# WSN_v2.net
KiCad netlist of a schematic drawn in Altium Designer
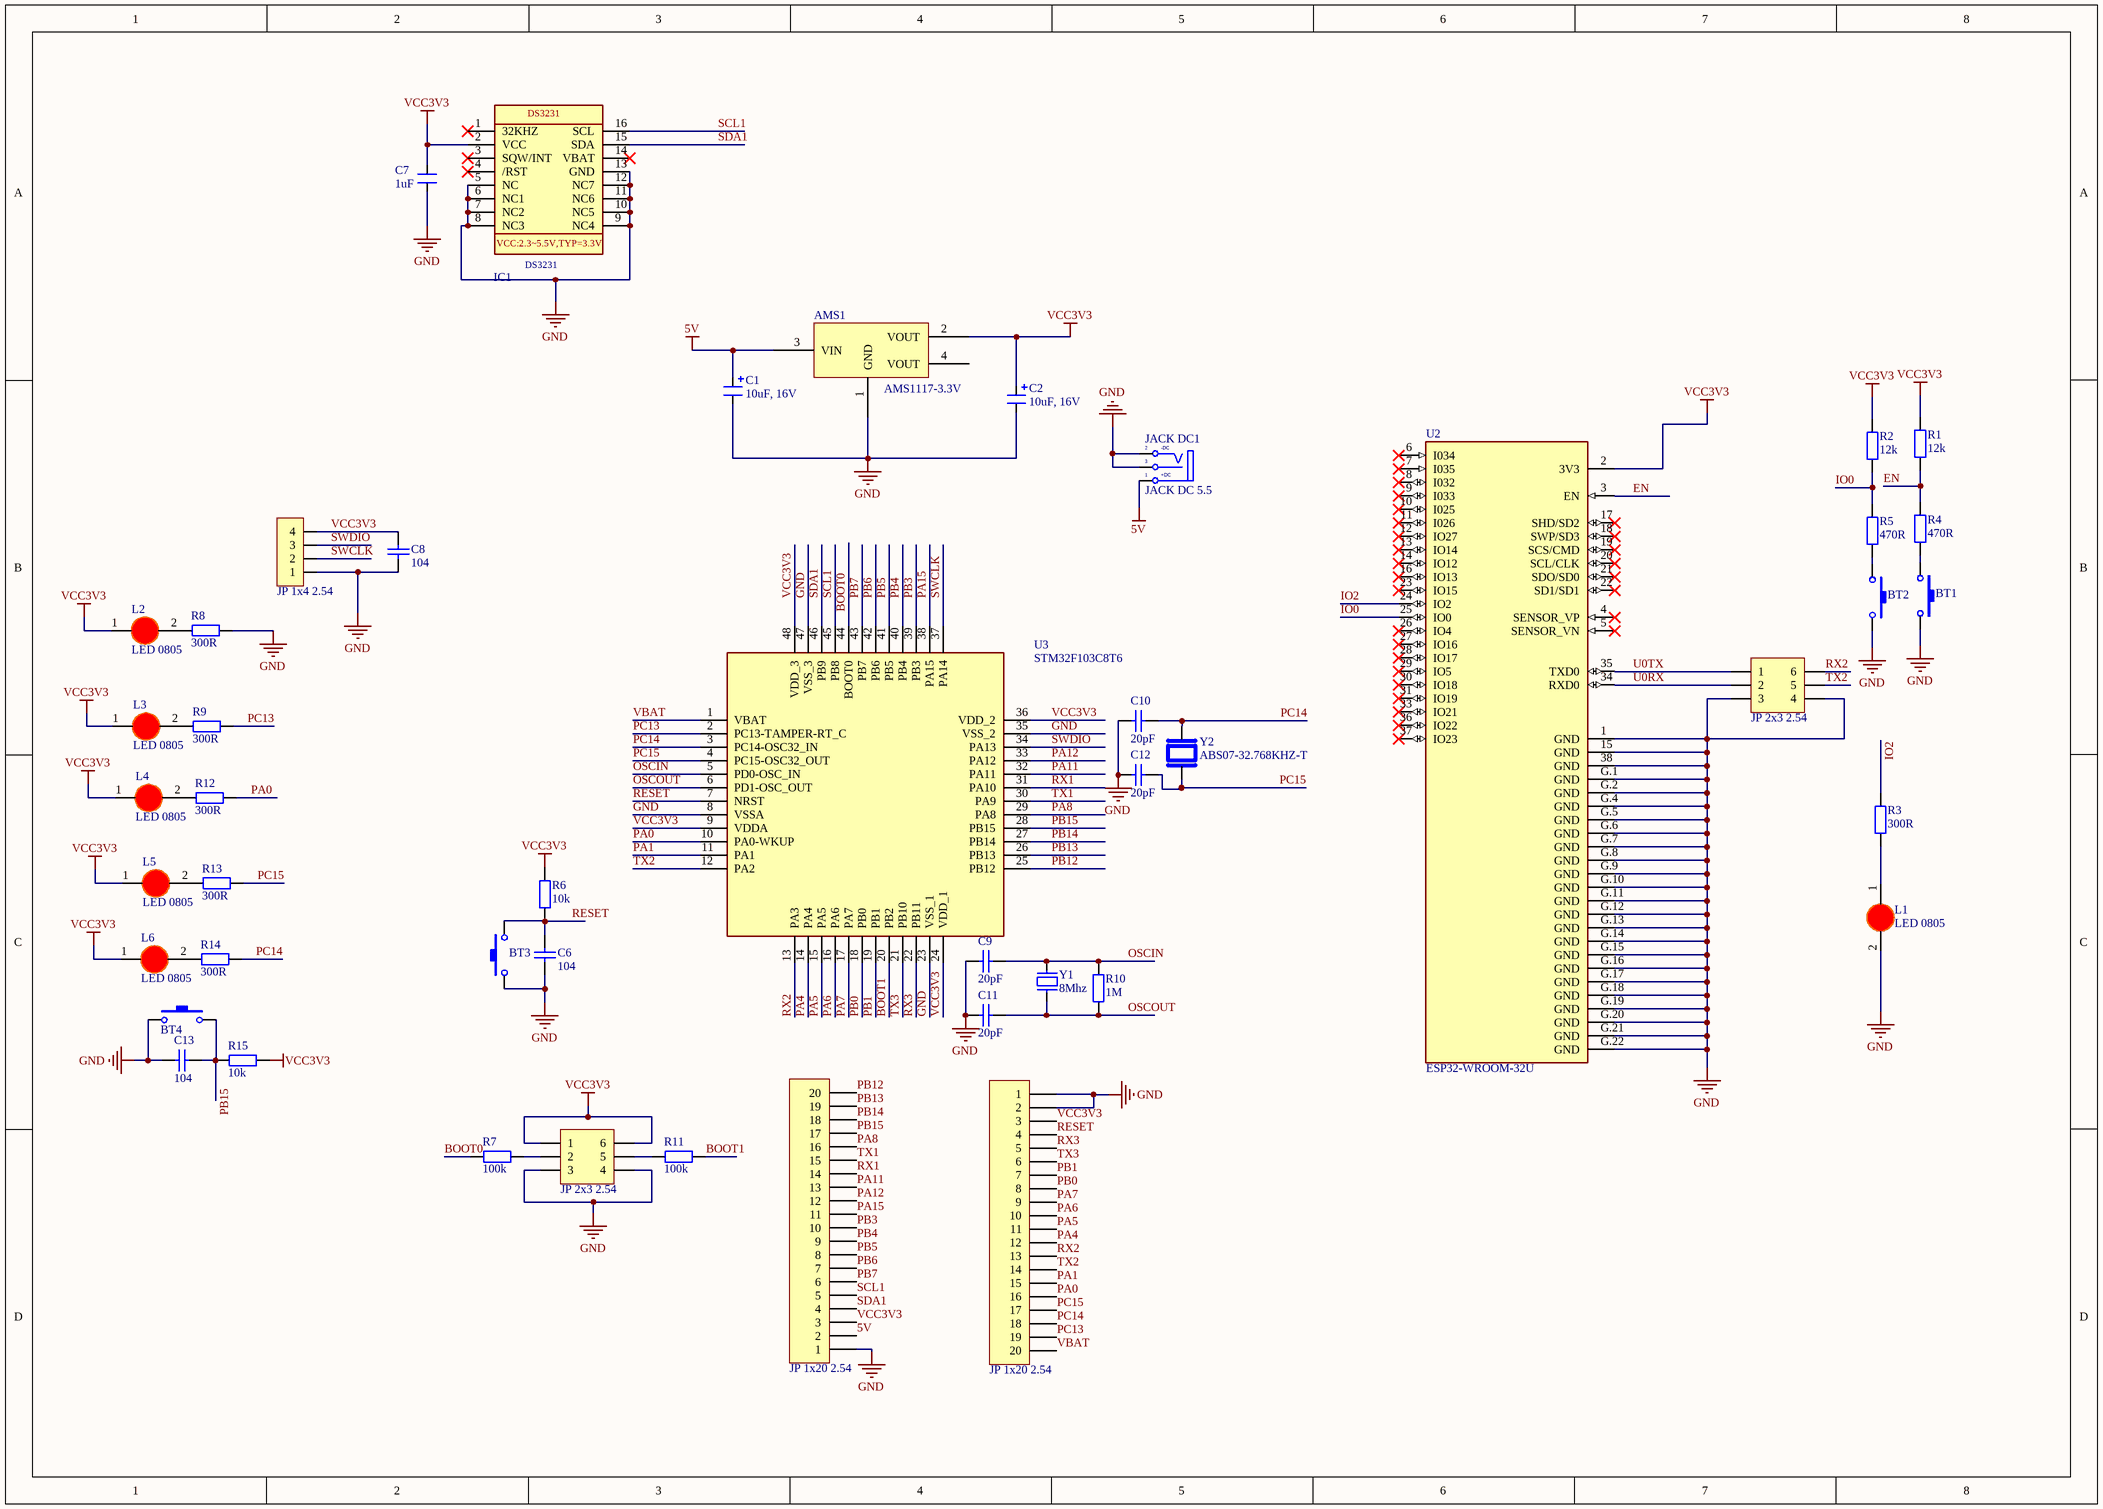
[diagram p0: WSN_v2.SchDoc]

(export (version "E")
  (design (tool "Eeschema 10.0.6"))
  (components
    (comp (ref "AMS1")
      (value "AMS1117-3.3V")
      (footprint "SOT223-4N")
      (description "Dán")
      (libsource (lib "THU VIEN SCH") (part "AMS1117"))
    )
    (comp (ref "BT1")
      (value "Nut Nhan 2 Chan SMD 3x6x2.5")
      (footprint "Nut Nhan 2 Chan SMD 3x6x2.5")
      (libsource (lib "Altium_Lib_by_KhueNguyenCreator") (part "Nut Nhan 2 Chan SMD 3x6x2.5"))
    )
    (comp (ref "BT2")
      (value "Nut Nhan 2 Chan SMD 3x6x2.5")
      (footprint "Nut Nhan 2 Chan SMD 3x6x2.5")
      (libsource (lib "Altium_Lib_by_KhueNguyenCreator") (part "Nut Nhan 2 Chan SMD 3x6x2.5"))
    )
    (comp (ref "BT3")
      (value "Nut Nhan 2 Chan SMD 3x6x2.5")
      (footprint "Nut Nhan 2 Chan SMD 3x6x2.5")
      (libsource (lib "Altium_Lib_by_KhueNguyenCreator") (part "Nut Nhan 2 Chan SMD 3x6x2.5"))
    )
    (comp (ref "BT4")
      (value "Nut Nhan 2 Chan SMD 3x6x2.5")
      (footprint "Nut Nhan 2 Chan SMD 3x6x2.5")
      (libsource (lib "Altium_Lib_by_KhueNguyenCreator") (part "Nut Nhan 2 Chan SMD 3x6x2.5"))
    )
    (comp (ref "C1")
      (value "10uF, 16V")
      (footprint "C_FC_10UF_16V")
      (description "Cap SMD, TANTALUM")
      (libsource (lib "quangnguyen") (part "CM-TANTALUM"))
    )
    (comp (ref "C2")
      (value "10uF, 16V")
      (footprint "C_FC_10UF_16V")
      (description "Cap SMD, TANTALUM")
      (libsource (lib "quangnguyen") (part "CM-TANTALUM"))
    )
    (comp (ref "C6")
      (value "104")
      (footprint "tu 0805")
      (description "Dán")
      (libsource (lib "DoAn2") (part "Tu 0805 104 50V 10%"))
    )
    (comp (ref "C7")
      (value "1uF")
      (footprint "Cap Ceramic 0805 SMD")
      (description "Cap SMD")
      (libsource (lib "quangnguyen_lib_altium") (part "CM"))
    )
    (comp (ref "C8")
      (value "104")
      (footprint "tu 0805")
      (description "Dán")
      (libsource (lib "DoAn2") (part "Tu 0805 104 50V 10%"))
    )
    (comp (ref "C9")
      (value "20pF")
      (footprint "tu 0805")
      (description "Dán")
      (libsource (lib "DoAn2") (part "Tu 0805 20pF 50V 10%"))
    )
    (comp (ref "C10")
      (value "20pF")
      (footprint "tu 0805")
      (description "Dán")
      (libsource (lib "DoAn2") (part "Tu 0805 20pF 50V 10%"))
    )
    (comp (ref "C11")
      (value "20pF")
      (footprint "tu 0805")
      (description "Dán")
      (libsource (lib "DoAn2") (part "Tu 0805 20pF 50V 10%"))
    )
    (comp (ref "C12")
      (value "20pF")
      (footprint "tu 0805")
      (description "Dán")
      (libsource (lib "DoAn2") (part "Tu 0805 20pF 50V 10%"))
    )
    (comp (ref "C13")
      (value "104")
      (footprint "tu 0805")
      (description "Dán")
      (libsource (lib "DoAn2") (part "Tu 0805 104 50V 10%"))
    )
    (comp (ref "IC1")
      (value "DS3231")
      (footprint "SOIC-16")
      (description "RTC DS3231")
      (fields (field (name "MF") "Maxim Integrated"))
      (libsource (lib "Board1") (part "DS3231"))
    )
    (comp (ref "JACK DC1")
      (value "JACK DC 5.5")
      (footprint "JACK DC 5.5")
      (libsource (lib "Altium_Lib_by_KhueNguyenCreator") (part "JACK DC 5.5"))
    )
    (comp (ref "JP1")
      (value "JP 1x4 2.54")
      (footprint "JP 1x4 DT")
      (description "Cắm")
      (libsource (lib "Altium_Lib_by_KhueNguyenCreator") (part "JP 1x4 2.54 Duc Thang"))
    )
    (comp (ref "JP2")
      (value "JP 2x3 2.54")
      (footprint "JP 2x3 DT")
      (description "Cắm")
      (libsource (lib "Altium_Lib_by_KhueNguyenCreator") (part "JP 2x3 2.54 Duc Thang"))
    )
    (comp (ref "JP3")
      (value "JP 1x20 2.54")
      (footprint "JP 1x20 DT")
      (description "Cắm")
      (libsource (lib "") (part "JP 1x20 2.54 Duc Thang_1"))
    )
    (comp (ref "JP4")
      (value "JP 1x20 2.54")
      (footprint "JP 1x20 DT")
      (description "Cắm")
      (libsource (lib "Altium_Lib_by_KhueNguyenCreator") (part "JP 1x20 2.54 Duc Thang"))
    )
    (comp (ref "JP5")
      (value "JP 2x3 2.54")
      (footprint "JP 2x3 DT")
      (description "Cắm")
      (libsource (lib "Altium_Lib_by_KhueNguyenCreator") (part "JP 2x3 2.54 Duc Thang"))
    )
    (comp (ref "L1")
      (value "LED 0805")
      (footprint "LED-1206-Red")
      (description "Dán")
      (libsource (lib "DoAn2") (part "LED 1206 Do"))
    )
    (comp (ref "L2")
      (value "LED 0805")
      (footprint "LED-1206-Red")
      (description "Dán")
      (libsource (lib "DoAn2") (part "LED 1206 Do"))
    )
    (comp (ref "L3")
      (value "LED 0805")
      (footprint "LED-1206-Red")
      (description "Dán")
      (libsource (lib "DoAn2") (part "LED 1206 Do"))
    )
    (comp (ref "L4")
      (value "LED 0805")
      (footprint "LED-1206-Red")
      (description "Dán")
      (libsource (lib "DoAn2") (part "LED 1206 Do"))
    )
    (comp (ref "L5")
      (value "LED 0805")
      (footprint "LED-1206-Red")
      (description "Dán")
      (libsource (lib "DoAn2") (part "LED 1206 Do"))
    )
    (comp (ref "L6")
      (value "LED 0805")
      (footprint "LED-1206-Red")
      (description "Dán")
      (libsource (lib "DoAn2") (part "LED 1206 Do"))
    )
    (comp (ref "R1")
      (value "12k")
      (footprint "tro smd 0805")
      (description "Dán")
      (libsource (lib "Altium_Lib_by_KhueNguyenCreator") (part "Tro 0805 1% 12k"))
    )
    (comp (ref "R2")
      (value "12k")
      (footprint "tro smd 0805")
      (description "Dán")
      (libsource (lib "Altium_Lib_by_KhueNguyenCreator") (part "Tro 0805 1% 12k"))
    )
    (comp (ref "R3")
      (value "300R")
      (footprint "Tro SMD 0805")
      (description "Dán")
      (libsource (lib "DoAn2") (part "Tro 0805 5% 300R"))
    )
    (comp (ref "R4")
      (value "470R")
      (footprint "Tro SMD 0805")
      (description "Dán")
      (libsource (lib "Altium_Lib_by_KhueNguyenCreator") (part "Tro 0805 5% 470R"))
    )
    (comp (ref "R5")
      (value "470R")
      (footprint "Tro SMD 0805")
      (description "Dán")
      (libsource (lib "Altium_Lib_by_KhueNguyenCreator") (part "Tro 0805 5% 470R"))
    )
    (comp (ref "R6")
      (value "10k")
      (footprint "tro smd 0805")
      (description "Dán")
      (libsource (lib "DoAn2") (part "Tro 0805 5% 10k"))
    )
    (comp (ref "R7")
      (value "100k")
      (footprint "tro smd 0805")
      (description "Dán")
      (libsource (lib "Altium_Lib_by_KhueNguyenCreator") (part "Tro 0805 5% 100k"))
    )
    (comp (ref "R8")
      (value "300R")
      (footprint "Tro SMD 0805")
      (description "Dán")
      (libsource (lib "DoAn2") (part "Tro 0805 5% 300R"))
    )
    (comp (ref "R9")
      (value "300R")
      (footprint "Tro SMD 0805")
      (description "Dán")
      (libsource (lib "DoAn2") (part "Tro 0805 5% 300R"))
    )
    (comp (ref "R10")
      (value "1M")
      (footprint "tro smd 0805")
      (description "Dán")
      (libsource (lib "DoAn2") (part "Tro 0805 5% 1M"))
    )
    (comp (ref "R11")
      (value "100k")
      (footprint "tro smd 0805")
      (description "Dán")
      (libsource (lib "Altium_Lib_by_KhueNguyenCreator") (part "Tro 0805 5% 100k"))
    )
    (comp (ref "R12")
      (value "300R")
      (footprint "Tro SMD 0805")
      (description "Dán")
      (libsource (lib "DoAn2") (part "Tro 0805 5% 300R"))
    )
    (comp (ref "R13")
      (value "300R")
      (footprint "Tro SMD 0805")
      (description "Dán")
      (libsource (lib "DoAn2") (part "Tro 0805 5% 300R"))
    )
    (comp (ref "R14")
      (value "300R")
      (footprint "Tro SMD 0805")
      (description "Dán")
      (libsource (lib "DoAn2") (part "Tro 0805 5% 300R"))
    )
    (comp (ref "R15")
      (value "10k")
      (footprint "tro smd 0805")
      (description "Dán")
      (libsource (lib "DoAn2") (part "Tro 0805 5% 10k"))
    )
    (comp (ref "U2")
      (value "ESP32-WROOM-32U")
      (footprint "XCVR_ESP32-WROOM-32U")
      (fields (field (name "MF") "Espressif Systems"))
      (libsource (lib "ESP32-WROOM-32U") (part "ESP32-WROOM-32U"))
    )
    (comp (ref "U3")
      (value "STM32F103C8T6")
      (footprint "LQFP-48_19.6_393_58X11_SMD")
      (description "ARM® Cortex®-M3 STM32F1 Microcontroller IC 32-Bit 72MHz 64KB (64K x 8) FLASH 48-LQFP (7x7)")
      (fields (field (name "MANUFACTURER") "STMicroelectronics"))
      (libsource (lib "DoAn2") (part "IC_STM32F103C8T6"))
    )
    (comp (ref "Y1")
      (value "8Mhz")
      (footprint "Thach Anh 2 chan SMD")
      (description "Crystal For all Crystal 2pin.")
      (libsource (lib "DoAn2") (part "Thach Anh 2 chan SMD"))
    )
    (comp (ref "Y2")
      (value "ABS07-32.768KHZ-T")
      (footprint "XTAL_ABS07-32.768KHZ-T")
      (description "32.768 kHz Â±20ppm Crystal 12.5pF 70 kOhms 2-SMD, No Lead")
      (fields (field (name "MF") "Abracon"))
      (libsource (lib "ABS07-32.768KHZ-T") (part "ABS07-32.768KHZ-T"))
    )
  )
  (nets
    (net (code "1") (name "/BOOT0") (class "Default")
      (node (ref "R7") (pin "1") (pinfunction "1_1") (pintype "passive"))
      (node (ref "U3") (pin "44") (pinfunction "BOOT0_44") (pintype "passive"))
    )
    (net (code "2") (name "/BOOT1") (class "Default")
      (node (ref "R11") (pin "2") (pinfunction "2_2") (pintype "passive"))
      (node (ref "U3") (pin "20") (pinfunction "PB2_20") (pintype "passive"))
    )
    (net (code "3") (name "/EN") (class "Default")
      (node (ref "R1") (pin "1") (pinfunction "1_1") (pintype "passive"))
      (node (ref "R4") (pin "2") (pinfunction "2_2") (pintype "passive"))
      (node (ref "U2") (pin "3") (pinfunction "EN_3") (pintype "input"))
    )
    (net (code "4") (name "/IO0") (class "Default")
      (node (ref "R2") (pin "1") (pinfunction "1_1") (pintype "passive"))
      (node (ref "R5") (pin "2") (pinfunction "2_2") (pintype "passive"))
      (node (ref "U2") (pin "25") (pinfunction "IO0_25") (pintype "bidirectional"))
    )
    (net (code "5") (name "/IO2") (class "Default")
      (node (ref "R3") (pin "1") (pinfunction "1_1") (pintype "passive"))
      (node (ref "U2") (pin "24") (pinfunction "IO2_24") (pintype "bidirectional"))
    )
    (net (code "6") (name "/OSCIN") (class "Default")
      (node (ref "C9") (pin "1") (pinfunction "1_1") (pintype "passive"))
      (node (ref "R10") (pin "2") (pinfunction "2_2") (pintype "passive"))
      (node (ref "U3") (pin "5") (pinfunction "PD0-OSC_IN_5") (pintype "passive"))
      (node (ref "Y1") (pin "2") (pinfunction "2_2") (pintype "passive"))
    )
    (net (code "7") (name "/OSCOUT") (class "Default")
      (node (ref "C11") (pin "1") (pinfunction "1_1") (pintype "passive"))
      (node (ref "R10") (pin "1") (pinfunction "1_1") (pintype "passive"))
      (node (ref "U3") (pin "6") (pinfunction "PD1-OSC_OUT_6") (pintype "passive"))
      (node (ref "Y1") (pin "1") (pinfunction "1_1") (pintype "passive"))
    )
    (net (code "8") (name "/PA0") (class "Default")
      (node (ref "JP4") (pin "16") (pinfunction "16_16") (pintype "passive"))
      (node (ref "R12") (pin "2") (pinfunction "2_2") (pintype "passive"))
      (node (ref "U3") (pin "10") (pinfunction "PA0-WKUP_10") (pintype "passive"))
    )
    (net (code "9") (name "/PA1") (class "Default")
      (node (ref "JP4") (pin "15") (pinfunction "15_15") (pintype "passive"))
      (node (ref "U3") (pin "11") (pinfunction "PA1_11") (pintype "passive"))
    )
    (net (code "10") (name "/PA4") (class "Default")
      (node (ref "JP4") (pin "12") (pinfunction "12_12") (pintype "passive"))
      (node (ref "U3") (pin "14") (pinfunction "PA4_14") (pintype "passive"))
    )
    (net (code "11") (name "/PA5") (class "Default")
      (node (ref "JP4") (pin "11") (pinfunction "11_11") (pintype "passive"))
      (node (ref "U3") (pin "15") (pinfunction "PA5_15") (pintype "passive"))
    )
    (net (code "12") (name "/PA6") (class "Default")
      (node (ref "JP4") (pin "10") (pinfunction "10_10") (pintype "passive"))
      (node (ref "U3") (pin "16") (pinfunction "PA6_16") (pintype "passive"))
    )
    (net (code "13") (name "/PA7") (class "Default")
      (node (ref "JP4") (pin "9") (pinfunction "9_9") (pintype "passive"))
      (node (ref "U3") (pin "17") (pinfunction "PA7_17") (pintype "passive"))
    )
    (net (code "14") (name "/PA8") (class "Default")
      (node (ref "JP3") (pin "16") (pinfunction "16_16") (pintype "passive"))
      (node (ref "U3") (pin "29") (pinfunction "PA8_29") (pintype "passive"))
    )
    (net (code "15") (name "/PA11") (class "Default")
      (node (ref "JP3") (pin "13") (pinfunction "13_13") (pintype "passive"))
      (node (ref "U3") (pin "32") (pinfunction "PA11_32") (pintype "passive"))
    )
    (net (code "16") (name "/PA12") (class "Default")
      (node (ref "JP3") (pin "12") (pinfunction "12_12") (pintype "passive"))
      (node (ref "U3") (pin "33") (pinfunction "PA12_33") (pintype "passive"))
    )
    (net (code "17") (name "/PA15") (class "Default")
      (node (ref "JP3") (pin "11") (pinfunction "11_11") (pintype "passive"))
      (node (ref "U3") (pin "38") (pinfunction "PA15_38") (pintype "passive"))
    )
    (net (code "18") (name "/PB0") (class "Default")
      (node (ref "JP4") (pin "8") (pinfunction "8_8") (pintype "passive"))
      (node (ref "U3") (pin "18") (pinfunction "PB0_18") (pintype "passive"))
    )
    (net (code "19") (name "/PB1") (class "Default")
      (node (ref "JP4") (pin "7") (pinfunction "7_7") (pintype "passive"))
      (node (ref "U3") (pin "19") (pinfunction "PB1_19") (pintype "passive"))
    )
    (net (code "20") (name "/PB3") (class "Default")
      (node (ref "JP3") (pin "10") (pinfunction "10_10") (pintype "passive"))
      (node (ref "U3") (pin "39") (pinfunction "PB3_39") (pintype "passive"))
    )
    (net (code "21") (name "/PB4") (class "Default")
      (node (ref "JP3") (pin "9") (pinfunction "9_9") (pintype "passive"))
      (node (ref "U3") (pin "40") (pinfunction "PB4_40") (pintype "passive"))
    )
    (net (code "22") (name "/PB5") (class "Default")
      (node (ref "JP3") (pin "8") (pinfunction "8_8") (pintype "passive"))
      (node (ref "U3") (pin "41") (pinfunction "PB5_41") (pintype "passive"))
    )
    (net (code "23") (name "/PB6") (class "Default")
      (node (ref "JP3") (pin "7") (pinfunction "7_7") (pintype "passive"))
      (node (ref "U3") (pin "42") (pinfunction "PB6_42") (pintype "passive"))
    )
    (net (code "24") (name "/PB7") (class "Default")
      (node (ref "JP3") (pin "6") (pinfunction "6_6") (pintype "passive"))
      (node (ref "U3") (pin "43") (pinfunction "PB7_43") (pintype "passive"))
    )
    (net (code "25") (name "/PB12") (class "Default")
      (node (ref "JP3") (pin "20") (pinfunction "20_20") (pintype "passive"))
      (node (ref "U3") (pin "25") (pinfunction "PB12_25") (pintype "passive"))
    )
    (net (code "26") (name "/PB13") (class "Default")
      (node (ref "JP3") (pin "19") (pinfunction "19_19") (pintype "passive"))
      (node (ref "U3") (pin "26") (pinfunction "PB13_26") (pintype "passive"))
    )
    (net (code "27") (name "/PB14") (class "Default")
      (node (ref "JP3") (pin "18") (pinfunction "18_18") (pintype "passive"))
      (node (ref "U3") (pin "27") (pinfunction "PB14_27") (pintype "passive"))
    )
    (net (code "28") (name "/PB15") (class "Default")
      (node (ref "BT4") (pin "2") (pinfunction "2_2") (pintype "passive"))
      (node (ref "C13") (pin "1") (pinfunction "1_1") (pintype "passive"))
      (node (ref "JP3") (pin "17") (pinfunction "17_17") (pintype "passive"))
      (node (ref "R15") (pin "1") (pinfunction "1_1") (pintype "passive"))
      (node (ref "U3") (pin "28") (pinfunction "PB15_28") (pintype "passive"))
    )
    (net (code "29") (name "/PC13") (class "Default")
      (node (ref "JP4") (pin "19") (pinfunction "19_19") (pintype "passive"))
      (node (ref "R9") (pin "2") (pinfunction "2_2") (pintype "passive"))
      (node (ref "U3") (pin "2") (pinfunction "PC13-TAMPER-RT_C_2") (pintype "passive"))
    )
    (net (code "30") (name "/PC14") (class "Default")
      (node (ref "C10") (pin "1") (pinfunction "1_1") (pintype "passive"))
      (node (ref "JP4") (pin "18") (pinfunction "18_18") (pintype "passive"))
      (node (ref "R14") (pin "2") (pinfunction "2_2") (pintype "passive"))
      (node (ref "U3") (pin "3") (pinfunction "PC14-OSC32_IN_3") (pintype "passive"))
      (node (ref "Y2") (pin "2") (pinfunction "2_2") (pintype "passive"))
    )
    (net (code "31") (name "/PC15") (class "Default")
      (node (ref "C12") (pin "1") (pinfunction "1_1") (pintype "passive"))
      (node (ref "JP4") (pin "17") (pinfunction "17_17") (pintype "passive"))
      (node (ref "R13") (pin "2") (pinfunction "2_2") (pintype "passive"))
      (node (ref "U3") (pin "4") (pinfunction "PC15-OSC32_OUT_4") (pintype "passive"))
      (node (ref "Y2") (pin "1") (pinfunction "1_1") (pintype "passive"))
    )
    (net (code "32") (name "/RESET") (class "Default")
      (node (ref "BT3") (pin "2") (pinfunction "2_2") (pintype "passive"))
      (node (ref "C6") (pin "1") (pinfunction "1_1") (pintype "passive"))
      (node (ref "JP4") (pin "4") (pinfunction "4_4") (pintype "passive"))
      (node (ref "R6") (pin "1") (pinfunction "1_1") (pintype "passive"))
      (node (ref "U3") (pin "7") (pinfunction "NRST_7") (pintype "passive"))
    )
    (net (code "33") (name "/RX1") (class "Default")
      (node (ref "JP3") (pin "14") (pinfunction "14_14") (pintype "passive"))
      (node (ref "U3") (pin "31") (pinfunction "PA10_31") (pintype "passive"))
    )
    (net (code "34") (name "/RX2") (class "Default")
      (node (ref "JP4") (pin "13") (pinfunction "13_13") (pintype "passive"))
      (node (ref "JP5") (pin "6") (pinfunction "6_6") (pintype "passive"))
      (node (ref "U3") (pin "13") (pinfunction "PA3_13") (pintype "passive"))
    )
    (net (code "35") (name "/RX3") (class "Default")
      (node (ref "JP4") (pin "5") (pinfunction "5_5") (pintype "passive"))
      (node (ref "U3") (pin "22") (pinfunction "PB11_22") (pintype "passive"))
    )
    (net (code "36") (name "/SCL1") (class "Default")
      (node (ref "IC1") (pin "16") (pinfunction "SCL_16") (pintype "passive"))
      (node (ref "JP3") (pin "5") (pinfunction "5_5") (pintype "passive"))
      (node (ref "U3") (pin "45") (pinfunction "PB8_45") (pintype "passive"))
    )
    (net (code "37") (name "/SDA1") (class "Default")
      (node (ref "IC1") (pin "15") (pinfunction "SDA_15") (pintype "passive"))
      (node (ref "JP3") (pin "4") (pinfunction "4_4") (pintype "passive"))
      (node (ref "U3") (pin "46") (pinfunction "PB9_46") (pintype "passive"))
    )
    (net (code "38") (name "/SWCLK") (class "Default")
      (node (ref "JP1") (pin "2") (pinfunction "2_2") (pintype "passive"))
      (node (ref "U3") (pin "37") (pinfunction "PA14_37") (pintype "passive"))
    )
    (net (code "39") (name "/SWDIO") (class "Default")
      (node (ref "JP1") (pin "3") (pinfunction "3_3") (pintype "passive"))
      (node (ref "U3") (pin "34") (pinfunction "PA13_34") (pintype "passive"))
    )
    (net (code "40") (name "/TX1") (class "Default")
      (node (ref "JP3") (pin "15") (pinfunction "15_15") (pintype "passive"))
      (node (ref "U3") (pin "30") (pinfunction "PA9_30") (pintype "passive"))
    )
    (net (code "41") (name "/TX2") (class "Default")
      (node (ref "JP4") (pin "14") (pinfunction "14_14") (pintype "passive"))
      (node (ref "JP5") (pin "5") (pinfunction "5_5") (pintype "passive"))
      (node (ref "U3") (pin "12") (pinfunction "PA2_12") (pintype "passive"))
    )
    (net (code "42") (name "/TX3") (class "Default")
      (node (ref "JP4") (pin "6") (pinfunction "6_6") (pintype "passive"))
      (node (ref "U3") (pin "21") (pinfunction "PB10_21") (pintype "passive"))
    )
    (net (code "43") (name "/U0RX") (class "Default")
      (node (ref "JP5") (pin "2") (pinfunction "2_2") (pintype "passive"))
      (node (ref "U2") (pin "34") (pinfunction "RXD0_34") (pintype "bidirectional"))
    )
    (net (code "44") (name "/U0TX") (class "Default")
      (node (ref "JP5") (pin "1") (pinfunction "1_1") (pintype "passive"))
      (node (ref "U2") (pin "35") (pinfunction "TXD0_35") (pintype "bidirectional"))
    )
    (net (code "45") (name "/VBAT") (class "Default")
      (node (ref "JP4") (pin "20") (pinfunction "20_20") (pintype "passive"))
      (node (ref "U3") (pin "1") (pinfunction "VBAT_1") (pintype "passive"))
    )
    (net (code "46") (name "5V") (class "Default")
      (node (ref "AMS1") (pin "3") (pinfunction "VIN_3") (pintype "passive"))
      (node (ref "C1") (pin "1") (pinfunction "1_1") (pintype "passive"))
      (node (ref "JACK DC1") (pin "1") (pinfunction "T_1") (pintype "passive"))
      (node (ref "JP3") (pin "2") (pinfunction "2_2") (pintype "passive"))
    )
    (net (code "47") (name "GND") (class "Default")
      (node (ref "AMS1") (pin "1") (pinfunction "GND_1") (pintype "passive"))
      (node (ref "BT1") (pin "2") (pinfunction "2_2") (pintype "passive"))
      (node (ref "BT2") (pin "2") (pinfunction "2_2") (pintype "passive"))
      (node (ref "BT3") (pin "1") (pinfunction "1_1") (pintype "passive"))
      (node (ref "BT4") (pin "1") (pinfunction "1_1") (pintype "passive"))
      (node (ref "C1") (pin "2") (pinfunction "2_2") (pintype "passive"))
      (node (ref "C10") (pin "2") (pinfunction "2_2") (pintype "passive"))
      (node (ref "C11") (pin "2") (pinfunction "2_2") (pintype "passive"))
      (node (ref "C12") (pin "2") (pinfunction "2_2") (pintype "passive"))
      (node (ref "C13") (pin "2") (pinfunction "2_2") (pintype "passive"))
      (node (ref "C2") (pin "2") (pinfunction "2_2") (pintype "passive"))
      (node (ref "C6") (pin "2") (pinfunction "2_2") (pintype "passive"))
      (node (ref "C7") (pin "1") (pinfunction "1_1") (pintype "passive"))
      (node (ref "C8") (pin "2") (pinfunction "2_2") (pintype "passive"))
      (node (ref "C9") (pin "2") (pinfunction "2_2") (pintype "passive"))
      (node (ref "IC1") (pin "10") (pinfunction "NC5_10") (pintype "passive"))
      (node (ref "IC1") (pin "11") (pinfunction "NC6_11") (pintype "passive"))
      (node (ref "IC1") (pin "12") (pinfunction "NC7_12") (pintype "passive"))
      (node (ref "IC1") (pin "13") (pinfunction "GND_13") (pintype "power_in"))
      (node (ref "IC1") (pin "5") (pinfunction "NC_5") (pintype "passive"))
      (node (ref "IC1") (pin "6") (pinfunction "NC1_6") (pintype "passive"))
      (node (ref "IC1") (pin "7") (pinfunction "NC2_7") (pintype "passive"))
      (node (ref "IC1") (pin "8") (pinfunction "NC3_8") (pintype "passive"))
      (node (ref "IC1") (pin "9") (pinfunction "NC4_9") (pintype "passive"))
      (node (ref "JACK DC1") (pin "2") (pinfunction "TN_2") (pintype "passive"))
      (node (ref "JACK DC1") (pin "3") (pinfunction "S_3") (pintype "power_in"))
      (node (ref "JP1") (pin "1") (pinfunction "1_1") (pintype "passive"))
      (node (ref "JP2") (pin "3") (pinfunction "3_3") (pintype "passive"))
      (node (ref "JP2") (pin "4") (pinfunction "4_4") (pintype "passive"))
      (node (ref "JP3") (pin "1") (pinfunction "1_1") (pintype "passive"))
      (node (ref "JP4") (pin "1") (pinfunction "1_1") (pintype "passive"))
      (node (ref "JP4") (pin "2") (pinfunction "2_2") (pintype "passive"))
      (node (ref "JP5") (pin "3") (pinfunction "3_3") (pintype "passive"))
      (node (ref "JP5") (pin "4") (pinfunction "4_4") (pintype "passive"))
      (node (ref "L1") (pin "2") (pinfunction "K_2") (pintype "passive"))
      (node (ref "R8") (pin "2") (pinfunction "2_2") (pintype "passive"))
      (node (ref "U2") (pin "1") (pinfunction "GND_1") (pintype "power_in"))
      (node (ref "U2") (pin "15") (pinfunction "GND_15") (pintype "power_in"))
      (node (ref "U2") (pin "38") (pinfunction "GND_38") (pintype "power_in"))
      (node (ref "U2") (pin "G.1") (pinfunction "GND_G.1") (pintype "power_in"))
      (node (ref "U2") (pin "G.10") (pinfunction "GND_G.10") (pintype "power_in"))
      (node (ref "U2") (pin "G.11") (pinfunction "GND_G.11") (pintype "power_in"))
      (node (ref "U2") (pin "G.12") (pinfunction "GND_G.12") (pintype "power_in"))
      (node (ref "U2") (pin "G.13") (pinfunction "GND_G.13") (pintype "power_in"))
      (node (ref "U2") (pin "G.14") (pinfunction "GND_G.14") (pintype "power_in"))
      (node (ref "U2") (pin "G.15") (pinfunction "GND_G.15") (pintype "power_in"))
      (node (ref "U2") (pin "G.16") (pinfunction "GND_G.16") (pintype "power_in"))
      (node (ref "U2") (pin "G.17") (pinfunction "GND_G.17") (pintype "power_in"))
      (node (ref "U2") (pin "G.18") (pinfunction "GND_G.18") (pintype "power_in"))
      (node (ref "U2") (pin "G.19") (pinfunction "GND_G.19") (pintype "power_in"))
      (node (ref "U2") (pin "G.2") (pinfunction "GND_G.2") (pintype "power_in"))
      (node (ref "U2") (pin "G.20") (pinfunction "GND_G.20") (pintype "power_in"))
      (node (ref "U2") (pin "G.21") (pinfunction "GND_G.21") (pintype "power_in"))
      (node (ref "U2") (pin "G.22") (pinfunction "GND_G.22") (pintype "power_in"))
      (node (ref "U2") (pin "G.4") (pinfunction "GND_G.4") (pintype "power_in"))
      (node (ref "U2") (pin "G.5") (pinfunction "GND_G.5") (pintype "power_in"))
      (node (ref "U2") (pin "G.6") (pinfunction "GND_G.6") (pintype "power_in"))
      (node (ref "U2") (pin "G.7") (pinfunction "GND_G.7") (pintype "power_in"))
      (node (ref "U2") (pin "G.8") (pinfunction "GND_G.8") (pintype "power_in"))
      (node (ref "U2") (pin "G.9") (pinfunction "GND_G.9") (pintype "power_in"))
      (node (ref "U3") (pin "23") (pinfunction "VSS_1_23") (pintype "passive"))
      (node (ref "U3") (pin "35") (pinfunction "VSS_2_35") (pintype "passive"))
      (node (ref "U3") (pin "47") (pinfunction "VSS_3_47") (pintype "passive"))
      (node (ref "U3") (pin "8") (pinfunction "VSSA_8") (pintype "passive"))
    )
    (net (code "48") (name "Net-(BT1-Pad1)") (class "Default")
      (node (ref "BT1") (pin "1") (pinfunction "1_1") (pintype "passive"))
      (node (ref "R4") (pin "1") (pinfunction "1_1") (pintype "passive"))
    )
    (net (code "49") (name "Net-(BT2-Pad1)") (class "Default")
      (node (ref "BT2") (pin "1") (pinfunction "1_1") (pintype "passive"))
      (node (ref "R5") (pin "1") (pinfunction "1_1") (pintype "passive"))
    )
    (net (code "50") (name "Net-(JP2-Pad2)") (class "Default")
      (node (ref "JP2") (pin "2") (pinfunction "2_2") (pintype "passive"))
      (node (ref "R7") (pin "2") (pinfunction "2_2") (pintype "passive"))
    )
    (net (code "51") (name "Net-(JP2-Pad5)") (class "Default")
      (node (ref "JP2") (pin "5") (pinfunction "5_5") (pintype "passive"))
      (node (ref "R11") (pin "1") (pinfunction "1_1") (pintype "passive"))
    )
    (net (code "52") (name "Net-(L1-A)") (class "Default")
      (node (ref "L1") (pin "1") (pinfunction "A_1") (pintype "passive"))
      (node (ref "R3") (pin "2") (pinfunction "2_2") (pintype "passive"))
    )
    (net (code "53") (name "Net-(L2-K)") (class "Default")
      (node (ref "L2") (pin "2") (pinfunction "K_2") (pintype "passive"))
      (node (ref "R8") (pin "1") (pinfunction "1_1") (pintype "passive"))
    )
    (net (code "54") (name "Net-(L3-K)") (class "Default")
      (node (ref "L3") (pin "2") (pinfunction "K_2") (pintype "passive"))
      (node (ref "R9") (pin "1") (pinfunction "1_1") (pintype "passive"))
    )
    (net (code "55") (name "Net-(L4-K)") (class "Default")
      (node (ref "L4") (pin "2") (pinfunction "K_2") (pintype "passive"))
      (node (ref "R12") (pin "1") (pinfunction "1_1") (pintype "passive"))
    )
    (net (code "56") (name "Net-(L5-K)") (class "Default")
      (node (ref "L5") (pin "2") (pinfunction "K_2") (pintype "passive"))
      (node (ref "R13") (pin "1") (pinfunction "1_1") (pintype "passive"))
    )
    (net (code "57") (name "Net-(L6-K)") (class "Default")
      (node (ref "L6") (pin "2") (pinfunction "K_2") (pintype "passive"))
      (node (ref "R14") (pin "1") (pinfunction "1_1") (pintype "passive"))
    )
    (net (code "58") (name "VCC3V3") (class "Default")
      (node (ref "AMS1") (pin "2") (pinfunction "VOUT_2") (pintype "passive"))
      (node (ref "C2") (pin "1") (pinfunction "1_1") (pintype "passive"))
      (node (ref "C7") (pin "2") (pinfunction "2_2") (pintype "passive"))
      (node (ref "C8") (pin "1") (pinfunction "1_1") (pintype "passive"))
      (node (ref "IC1") (pin "2") (pinfunction "VCC_2") (pintype "power_in"))
      (node (ref "JP1") (pin "4") (pinfunction "4_4") (pintype "passive"))
      (node (ref "JP2") (pin "1") (pinfunction "1_1") (pintype "passive"))
      (node (ref "JP2") (pin "6") (pinfunction "6_6") (pintype "passive"))
      (node (ref "JP3") (pin "3") (pinfunction "3_3") (pintype "passive"))
      (node (ref "JP4") (pin "3") (pinfunction "3_3") (pintype "passive"))
      (node (ref "L2") (pin "1") (pinfunction "A_1") (pintype "passive"))
      (node (ref "L3") (pin "1") (pinfunction "A_1") (pintype "passive"))
      (node (ref "L4") (pin "1") (pinfunction "A_1") (pintype "passive"))
      (node (ref "L5") (pin "1") (pinfunction "A_1") (pintype "passive"))
      (node (ref "L6") (pin "1") (pinfunction "A_1") (pintype "passive"))
      (node (ref "R1") (pin "2") (pinfunction "2_2") (pintype "passive"))
      (node (ref "R15") (pin "2") (pinfunction "2_2") (pintype "passive"))
      (node (ref "R2") (pin "2") (pinfunction "2_2") (pintype "passive"))
      (node (ref "R6") (pin "2") (pinfunction "2_2") (pintype "passive"))
      (node (ref "U2") (pin "2") (pinfunction "3V3_2") (pintype "power_in"))
      (node (ref "U3") (pin "24") (pinfunction "VDD_1_24") (pintype "passive"))
      (node (ref "U3") (pin "36") (pinfunction "VDD_2_36") (pintype "passive"))
      (node (ref "U3") (pin "48") (pinfunction "VDD_3_48") (pintype "passive"))
      (node (ref "U3") (pin "9") (pinfunction "VDDA_9") (pintype "passive"))
    )
    (net (code "59") (name "unconnected-(AMS1-VOUT-Pad4)") (class "Default")
      (node (ref "AMS1") (pin "4") (pinfunction "VOUT_4") (pintype "passive"))
    )
    (net (code "60") (name "unconnected-(IC1-32KHZ-Pad1)") (class "Default")
      (node (ref "IC1") (pin "1") (pinfunction "32KHZ_1") (pintype "passive+no_connect"))
    )
    (net (code "61") (name "unconnected-(IC1-SQW{slash}INT-Pad3)") (class "Default")
      (node (ref "IC1") (pin "3") (pinfunction "SQW/INT_3") (pintype "passive+no_connect"))
    )
    (net (code "62") (name "unconnected-(IC1-VBAT-Pad14)") (class "Default")
      (node (ref "IC1") (pin "14") (pinfunction "VBAT_14") (pintype "power_in+no_connect"))
    )
    (net (code "63") (name "unconnected-(IC1-{slash}RST-Pad4)") (class "Default")
      (node (ref "IC1") (pin "4") (pinfunction "/RST_4") (pintype "passive+no_connect"))
    )
    (net (code "64") (name "unconnected-(U2-I025-Pad10)") (class "Default")
      (node (ref "U2") (pin "10") (pinfunction "I025_10") (pintype "bidirectional+no_connect"))
    )
    (net (code "65") (name "unconnected-(U2-I026-Pad11)") (class "Default")
      (node (ref "U2") (pin "11") (pinfunction "I026_11") (pintype "bidirectional+no_connect"))
    )
    (net (code "66") (name "unconnected-(U2-I032-Pad8)") (class "Default")
      (node (ref "U2") (pin "8") (pinfunction "I032_8") (pintype "bidirectional+no_connect"))
    )
    (net (code "67") (name "unconnected-(U2-I033-Pad9)") (class "Default")
      (node (ref "U2") (pin "9") (pinfunction "I033_9") (pintype "bidirectional+no_connect"))
    )
    (net (code "68") (name "unconnected-(U2-I034-Pad6)") (class "Default")
      (node (ref "U2") (pin "6") (pinfunction "I034_6") (pintype "input+no_connect"))
    )
    (net (code "69") (name "unconnected-(U2-I035-Pad7)") (class "Default")
      (node (ref "U2") (pin "7") (pinfunction "I035_7") (pintype "input+no_connect"))
    )
    (net (code "70") (name "unconnected-(U2-IO4-Pad26)") (class "Default")
      (node (ref "U2") (pin "26") (pinfunction "IO4_26") (pintype "bidirectional+no_connect"))
    )
    (net (code "71") (name "unconnected-(U2-IO5-Pad29)") (class "Default")
      (node (ref "U2") (pin "29") (pinfunction "IO5_29") (pintype "bidirectional+no_connect"))
    )
    (net (code "72") (name "unconnected-(U2-IO12-Pad14)") (class "Default")
      (node (ref "U2") (pin "14") (pinfunction "IO12_14") (pintype "bidirectional+no_connect"))
    )
    (net (code "73") (name "unconnected-(U2-IO13-Pad16)") (class "Default")
      (node (ref "U2") (pin "16") (pinfunction "IO13_16") (pintype "bidirectional+no_connect"))
    )
    (net (code "74") (name "unconnected-(U2-IO14-Pad13)") (class "Default")
      (node (ref "U2") (pin "13") (pinfunction "IO14_13") (pintype "bidirectional+no_connect"))
    )
    (net (code "75") (name "unconnected-(U2-IO15-Pad23)") (class "Default")
      (node (ref "U2") (pin "23") (pinfunction "IO15_23") (pintype "bidirectional+no_connect"))
    )
    (net (code "76") (name "unconnected-(U2-IO16-Pad27)") (class "Default")
      (node (ref "U2") (pin "27") (pinfunction "IO16_27") (pintype "bidirectional+no_connect"))
    )
    (net (code "77") (name "unconnected-(U2-IO17-Pad28)") (class "Default")
      (node (ref "U2") (pin "28") (pinfunction "IO17_28") (pintype "bidirectional+no_connect"))
    )
    (net (code "78") (name "unconnected-(U2-IO18-Pad30)") (class "Default")
      (node (ref "U2") (pin "30") (pinfunction "IO18_30") (pintype "bidirectional+no_connect"))
    )
    (net (code "79") (name "unconnected-(U2-IO19-Pad31)") (class "Default")
      (node (ref "U2") (pin "31") (pinfunction "IO19_31") (pintype "bidirectional+no_connect"))
    )
    (net (code "80") (name "unconnected-(U2-IO21-Pad33)") (class "Default")
      (node (ref "U2") (pin "33") (pinfunction "IO21_33") (pintype "bidirectional+no_connect"))
    )
    (net (code "81") (name "unconnected-(U2-IO22-Pad36)") (class "Default")
      (node (ref "U2") (pin "36") (pinfunction "IO22_36") (pintype "bidirectional+no_connect"))
    )
    (net (code "82") (name "unconnected-(U2-IO23-Pad37)") (class "Default")
      (node (ref "U2") (pin "37") (pinfunction "IO23_37") (pintype "bidirectional+no_connect"))
    )
    (net (code "83") (name "unconnected-(U2-IO27-Pad12)") (class "Default")
      (node (ref "U2") (pin "12") (pinfunction "IO27_12") (pintype "bidirectional+no_connect"))
    )
    (net (code "84") (name "unconnected-(U2-SCL{slash}CLK-Pad20)") (class "Default")
      (node (ref "U2") (pin "20") (pinfunction "SCL/CLK_20") (pintype "bidirectional+no_connect"))
    )
    (net (code "85") (name "unconnected-(U2-SCS{slash}CMD-Pad19)") (class "Default")
      (node (ref "U2") (pin "19") (pinfunction "SCS/CMD_19") (pintype "bidirectional+no_connect"))
    )
    (net (code "86") (name "unconnected-(U2-SD1{slash}SD1-Pad22)") (class "Default")
      (node (ref "U2") (pin "22") (pinfunction "SD1/SD1_22") (pintype "bidirectional+no_connect"))
    )
    (net (code "87") (name "unconnected-(U2-SDO{slash}SD0-Pad21)") (class "Default")
      (node (ref "U2") (pin "21") (pinfunction "SDO/SD0_21") (pintype "bidirectional+no_connect"))
    )
    (net (code "88") (name "unconnected-(U2-SENSOR_VN-Pad5)") (class "Default")
      (node (ref "U2") (pin "5") (pinfunction "SENSOR_VN_5") (pintype "input+no_connect"))
    )
    (net (code "89") (name "unconnected-(U2-SENSOR_VP-Pad4)") (class "Default")
      (node (ref "U2") (pin "4") (pinfunction "SENSOR_VP_4") (pintype "input+no_connect"))
    )
    (net (code "90") (name "unconnected-(U2-SHD{slash}SD2-Pad17)") (class "Default")
      (node (ref "U2") (pin "17") (pinfunction "SHD/SD2_17") (pintype "bidirectional+no_connect"))
    )
    (net (code "91") (name "unconnected-(U2-SWP{slash}SD3-Pad18)") (class "Default")
      (node (ref "U2") (pin "18") (pinfunction "SWP/SD3_18") (pintype "bidirectional+no_connect"))
    )
  )
)
